# shield.net
KiCad netlist of a schematic drawn in EAGLE
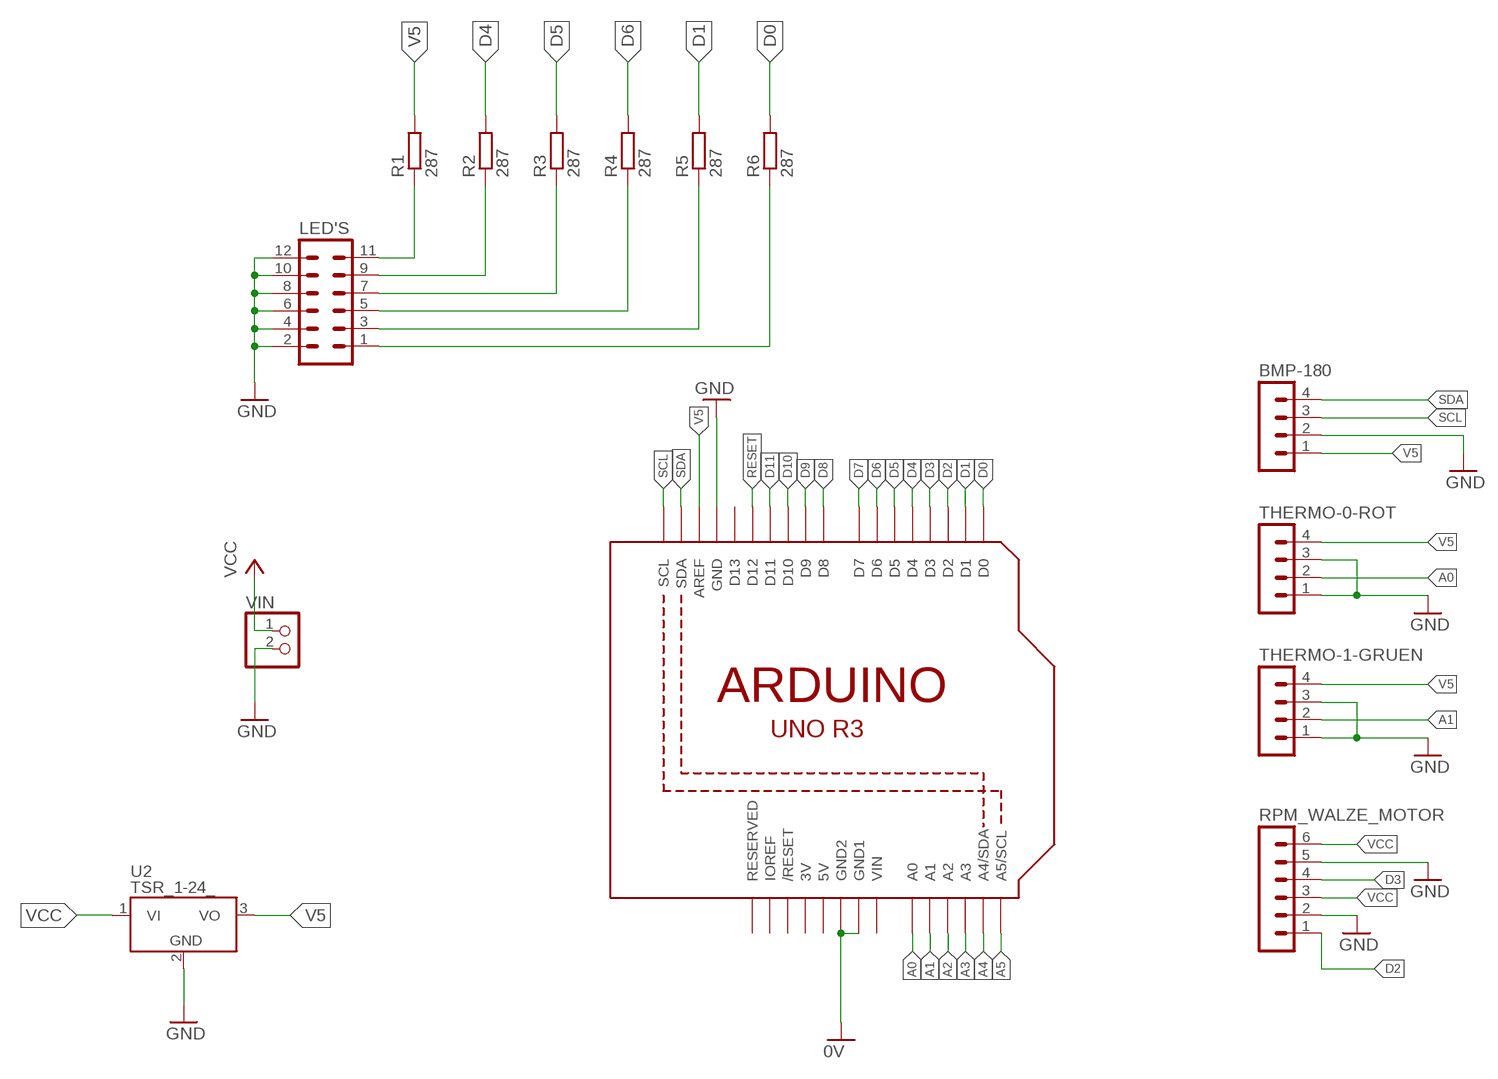
[diagram p0: schematic, sheet 1]

(export (version "E")
  (design (tool "Eeschema 10.0.6"))
  (components
    (comp (ref "BMP-180")
      (value "MA04-1")
      (footprint "eagle-import:MA04-1")
      (libsource (lib "eagle-import") (part "MA04-1"))
    )
    (comp (ref "LED'S")
      (value "MA06-2")
      (footprint "eagle-import:MA06-2")
      (libsource (lib "eagle-import") (part "MA06-2"))
    )
    (comp (ref "R1")
      (value "287")
      (footprint "eagle-import:0207_10")
      (libsource (lib "eagle-import") (part "R-EU_0207/10"))
    )
    (comp (ref "R2")
      (value "287")
      (footprint "eagle-import:0207_10")
      (libsource (lib "eagle-import") (part "R-EU_0207/10"))
    )
    (comp (ref "R3")
      (value "287")
      (footprint "eagle-import:0207_10")
      (libsource (lib "eagle-import") (part "R-EU_0207/10"))
    )
    (comp (ref "R4")
      (value "287")
      (footprint "eagle-import:0207_10")
      (libsource (lib "eagle-import") (part "R-EU_0207/10"))
    )
    (comp (ref "R5")
      (value "287")
      (footprint "eagle-import:0207_10")
      (libsource (lib "eagle-import") (part "R-EU_0207/10"))
    )
    (comp (ref "R6")
      (value "287")
      (footprint "eagle-import:0207_10")
      (libsource (lib "eagle-import") (part "R-EU_0207/10"))
    )
    (comp (ref "RPM_WALZE_MOTOR")
      (value "MA06-1")
      (footprint "eagle-import:MA06-1")
      (libsource (lib "eagle-import") (part "MA06-1"))
    )
    (comp (ref "THERMO-0-ROT")
      (value "MA04-1")
      (footprint "eagle-import:MA04-1")
      (libsource (lib "eagle-import") (part "MA04-1"))
    )
    (comp (ref "THERMO-1-GRUEN")
      (value "MA04-1")
      (footprint "eagle-import:MA04-1")
      (libsource (lib "eagle-import") (part "MA04-1"))
    )
    (comp (ref "U1")
      (value "ARDUINOR3-BPLACE")
      (footprint "eagle-import:ARDUINOR3-BPLACE")
      (libsource (lib "eagle-import") (part "ARDUINOR3-BPLACE"))
    )
    (comp (ref "U2")
      (value "TSR_1-24_")
      (footprint "eagle-import:TSR-1")
      (libsource (lib "eagle-import") (part "TSR_1-24_"))
    )
    (comp (ref "VIN")
      (value "PINHD-1X2")
      (footprint "eagle-import:1X02")
      (libsource (lib "eagle-import") (part "PINHD-1X2"))
    )
  )
  (nets
    (net (code "1") (name "/3V") (class "Default")
      (node (ref "U1") (pin "3V") (pinfunction "3V_3V") (pintype "power_in"))
    )
    (net (code "2") (name "/5V") (class "Default")
      (node (ref "U1") (pin "5V") (pinfunction "5V_5V") (pintype "power_in"))
    )
    (net (code "3") (name "/VIN") (class "Default")
      (node (ref "U1") (pin "VIN") (pinfunction "VIN_VIN") (pintype "power_in"))
    )
    (net (code "4") (name "0V") (class "Default")
      (node (ref "BMP-180") (pin "2") (pinfunction "2_2") (pintype "passive"))
      (node (ref "LED'S") (pin "10") (pinfunction "10_10") (pintype "passive"))
      (node (ref "LED'S") (pin "12") (pinfunction "12_12") (pintype "passive"))
      (node (ref "LED'S") (pin "2") (pinfunction "2_2") (pintype "passive"))
      (node (ref "LED'S") (pin "4") (pinfunction "4_4") (pintype "passive"))
      (node (ref "LED'S") (pin "6") (pinfunction "6_6") (pintype "passive"))
      (node (ref "LED'S") (pin "8") (pinfunction "8_8") (pintype "passive"))
      (node (ref "RPM_WALZE_MOTOR") (pin "2") (pinfunction "2_2") (pintype "passive"))
      (node (ref "RPM_WALZE_MOTOR") (pin "5") (pinfunction "5_5") (pintype "passive"))
      (node (ref "THERMO-0-ROT") (pin "1") (pinfunction "1_1") (pintype "passive"))
      (node (ref "THERMO-0-ROT") (pin "3") (pinfunction "3_3") (pintype "passive"))
      (node (ref "THERMO-1-GRUEN") (pin "1") (pinfunction "1_1") (pintype "passive"))
      (node (ref "THERMO-1-GRUEN") (pin "3") (pinfunction "3_3") (pintype "passive"))
      (node (ref "U1") (pin "GND") (pinfunction "GND_GND") (pintype "power_in"))
      (node (ref "U1") (pin "GND1") (pinfunction "GND1_GND1") (pintype "power_in"))
      (node (ref "U1") (pin "GND2") (pinfunction "GND2_GND2") (pintype "power_in"))
      (node (ref "U2") (pin "2") (pinfunction "GND_2") (pintype "power_in"))
      (node (ref "VIN") (pin "2") (pinfunction "2_2") (pintype "passive"))
    )
    (net (code "5") (name "A0") (class "Default")
      (node (ref "THERMO-0-ROT") (pin "2") (pinfunction "2_2") (pintype "passive"))
      (node (ref "U1") (pin "A0") (pinfunction "A0_A0") (pintype "bidirectional"))
    )
    (net (code "6") (name "A1") (class "Default")
      (node (ref "THERMO-1-GRUEN") (pin "2") (pinfunction "2_2") (pintype "passive"))
      (node (ref "U1") (pin "A1") (pinfunction "A1_A1") (pintype "bidirectional"))
    )
    (net (code "7") (name "A2") (class "Default")
      (node (ref "U1") (pin "A2") (pinfunction "A2_A2") (pintype "bidirectional"))
    )
    (net (code "8") (name "A3") (class "Default")
      (node (ref "U1") (pin "A3") (pinfunction "A3_A3") (pintype "bidirectional"))
    )
    (net (code "9") (name "A4") (class "Default")
      (node (ref "U1") (pin "A4") (pinfunction "A4/SDA_A4") (pintype "bidirectional"))
    )
    (net (code "10") (name "A5") (class "Default")
      (node (ref "U1") (pin "A5") (pinfunction "A5/SCL_A5") (pintype "bidirectional"))
    )
    (net (code "11") (name "D0") (class "Default")
      (node (ref "R6") (pin "2") (pinfunction "2_2") (pintype "passive"))
      (node (ref "U1") (pin "D0") (pinfunction "D0_D0") (pintype "bidirectional"))
    )
    (net (code "12") (name "D1") (class "Default")
      (node (ref "R5") (pin "2") (pinfunction "2_2") (pintype "passive"))
      (node (ref "U1") (pin "D1") (pinfunction "D1_D1") (pintype "bidirectional"))
    )
    (net (code "13") (name "D2") (class "Default")
      (node (ref "RPM_WALZE_MOTOR") (pin "1") (pinfunction "1_1") (pintype "passive"))
      (node (ref "U1") (pin "D2") (pinfunction "D2_D2") (pintype "bidirectional"))
    )
    (net (code "14") (name "D3") (class "Default")
      (node (ref "RPM_WALZE_MOTOR") (pin "4") (pinfunction "4_4") (pintype "passive"))
      (node (ref "U1") (pin "D3") (pinfunction "D3_D3") (pintype "bidirectional"))
    )
    (net (code "15") (name "D4") (class "Default")
      (node (ref "R2") (pin "2") (pinfunction "2_2") (pintype "passive"))
      (node (ref "U1") (pin "D4") (pinfunction "D4_D4") (pintype "bidirectional"))
    )
    (net (code "16") (name "D5") (class "Default")
      (node (ref "R3") (pin "2") (pinfunction "2_2") (pintype "passive"))
      (node (ref "U1") (pin "D5") (pinfunction "D5_D5") (pintype "bidirectional"))
    )
    (net (code "17") (name "D6") (class "Default")
      (node (ref "R4") (pin "2") (pinfunction "2_2") (pintype "passive"))
      (node (ref "U1") (pin "D6") (pinfunction "D6_D6") (pintype "bidirectional"))
    )
    (net (code "18") (name "D7") (class "Default")
      (node (ref "U1") (pin "D7") (pinfunction "D7_D7") (pintype "bidirectional"))
    )
    (net (code "19") (name "D8") (class "Default")
      (node (ref "U1") (pin "D8") (pinfunction "D8_D8") (pintype "bidirectional"))
    )
    (net (code "20") (name "D9") (class "Default")
      (node (ref "U1") (pin "D9") (pinfunction "D9_D9") (pintype "bidirectional"))
    )
    (net (code "21") (name "D10") (class "Default")
      (node (ref "U1") (pin "D10") (pinfunction "D10_D10") (pintype "bidirectional"))
    )
    (net (code "22") (name "D11") (class "Default")
      (node (ref "U1") (pin "D11") (pinfunction "D11_D11") (pintype "bidirectional"))
    )
    (net (code "23") (name "Net-(LED'S-Pad1)") (class "Default")
      (node (ref "LED'S") (pin "1") (pinfunction "1_1") (pintype "passive"))
      (node (ref "R6") (pin "1") (pinfunction "1_1") (pintype "passive"))
    )
    (net (code "24") (name "Net-(LED'S-Pad3)") (class "Default")
      (node (ref "LED'S") (pin "3") (pinfunction "3_3") (pintype "passive"))
      (node (ref "R5") (pin "1") (pinfunction "1_1") (pintype "passive"))
    )
    (net (code "25") (name "Net-(LED'S-Pad5)") (class "Default")
      (node (ref "LED'S") (pin "5") (pinfunction "5_5") (pintype "passive"))
      (node (ref "R4") (pin "1") (pinfunction "1_1") (pintype "passive"))
    )
    (net (code "26") (name "Net-(LED'S-Pad7)") (class "Default")
      (node (ref "LED'S") (pin "7") (pinfunction "7_7") (pintype "passive"))
      (node (ref "R3") (pin "1") (pinfunction "1_1") (pintype "passive"))
    )
    (net (code "27") (name "Net-(LED'S-Pad9)") (class "Default")
      (node (ref "LED'S") (pin "9") (pinfunction "9_9") (pintype "passive"))
      (node (ref "R2") (pin "1") (pinfunction "1_1") (pintype "passive"))
    )
    (net (code "28") (name "Net-(LED'S-Pad11)") (class "Default")
      (node (ref "LED'S") (pin "11") (pinfunction "11_11") (pintype "passive"))
      (node (ref "R1") (pin "1") (pinfunction "1_1") (pintype "passive"))
    )
    (net (code "29") (name "RESET") (class "Default")
      (node (ref "U1") (pin "D12") (pinfunction "D12_D12") (pintype "bidirectional"))
    )
    (net (code "30") (name "SCL") (class "Default")
      (node (ref "BMP-180") (pin "3") (pinfunction "3_3") (pintype "passive"))
      (node (ref "U1") (pin "SCL") (pinfunction "SCL_SCL") (pintype "bidirectional"))
    )
    (net (code "31") (name "SDA") (class "Default")
      (node (ref "BMP-180") (pin "4") (pinfunction "4_4") (pintype "passive"))
      (node (ref "U1") (pin "SDA") (pinfunction "SDA_SDA") (pintype "bidirectional"))
    )
    (net (code "32") (name "V5") (class "Default")
      (node (ref "BMP-180") (pin "1") (pinfunction "1_1") (pintype "passive"))
      (node (ref "R1") (pin "2") (pinfunction "2_2") (pintype "passive"))
      (node (ref "THERMO-0-ROT") (pin "4") (pinfunction "4_4") (pintype "passive"))
      (node (ref "THERMO-1-GRUEN") (pin "4") (pinfunction "4_4") (pintype "passive"))
      (node (ref "U1") (pin "AREF") (pinfunction "AREF_AREF") (pintype "bidirectional"))
      (node (ref "U2") (pin "3") (pinfunction "VO_3") (pintype "power_in"))
    )
    (net (code "33") (name "VCC") (class "Default")
      (node (ref "RPM_WALZE_MOTOR") (pin "3") (pinfunction "3_3") (pintype "passive"))
      (node (ref "RPM_WALZE_MOTOR") (pin "6") (pinfunction "6_6") (pintype "passive"))
      (node (ref "U2") (pin "1") (pinfunction "VI_1") (pintype "power_in"))
      (node (ref "VIN") (pin "1") (pinfunction "1_1") (pintype "passive"))
    )
    (net (code "34") (name "unconnected-(U1-PadD13)") (class "Default")
      (node (ref "U1") (pin "D13") (pinfunction "D13_D13") (pintype "bidirectional"))
    )
    (net (code "35") (name "unconnected-(U1-PadIOREF)") (class "Default")
      (node (ref "U1") (pin "IOREF") (pinfunction "IOREF_IOREF") (pintype "output"))
    )
    (net (code "36") (name "unconnected-(U1-PadRESERVED)") (class "Default")
      (node (ref "U1") (pin "RESERVED") (pinfunction "RESERVED_RESERVED") (pintype "no_connect"))
    )
    (net (code "37") (name "unconnected-(U1-{slash}RESET-PadRESET)") (class "Default")
      (node (ref "U1") (pin "RESET") (pinfunction "/RESET_RESET") (pintype "bidirectional"))
    )
  )
)
